# 3V3_REG.net
KiCad netlist of a schematic drawn in Altium Designer
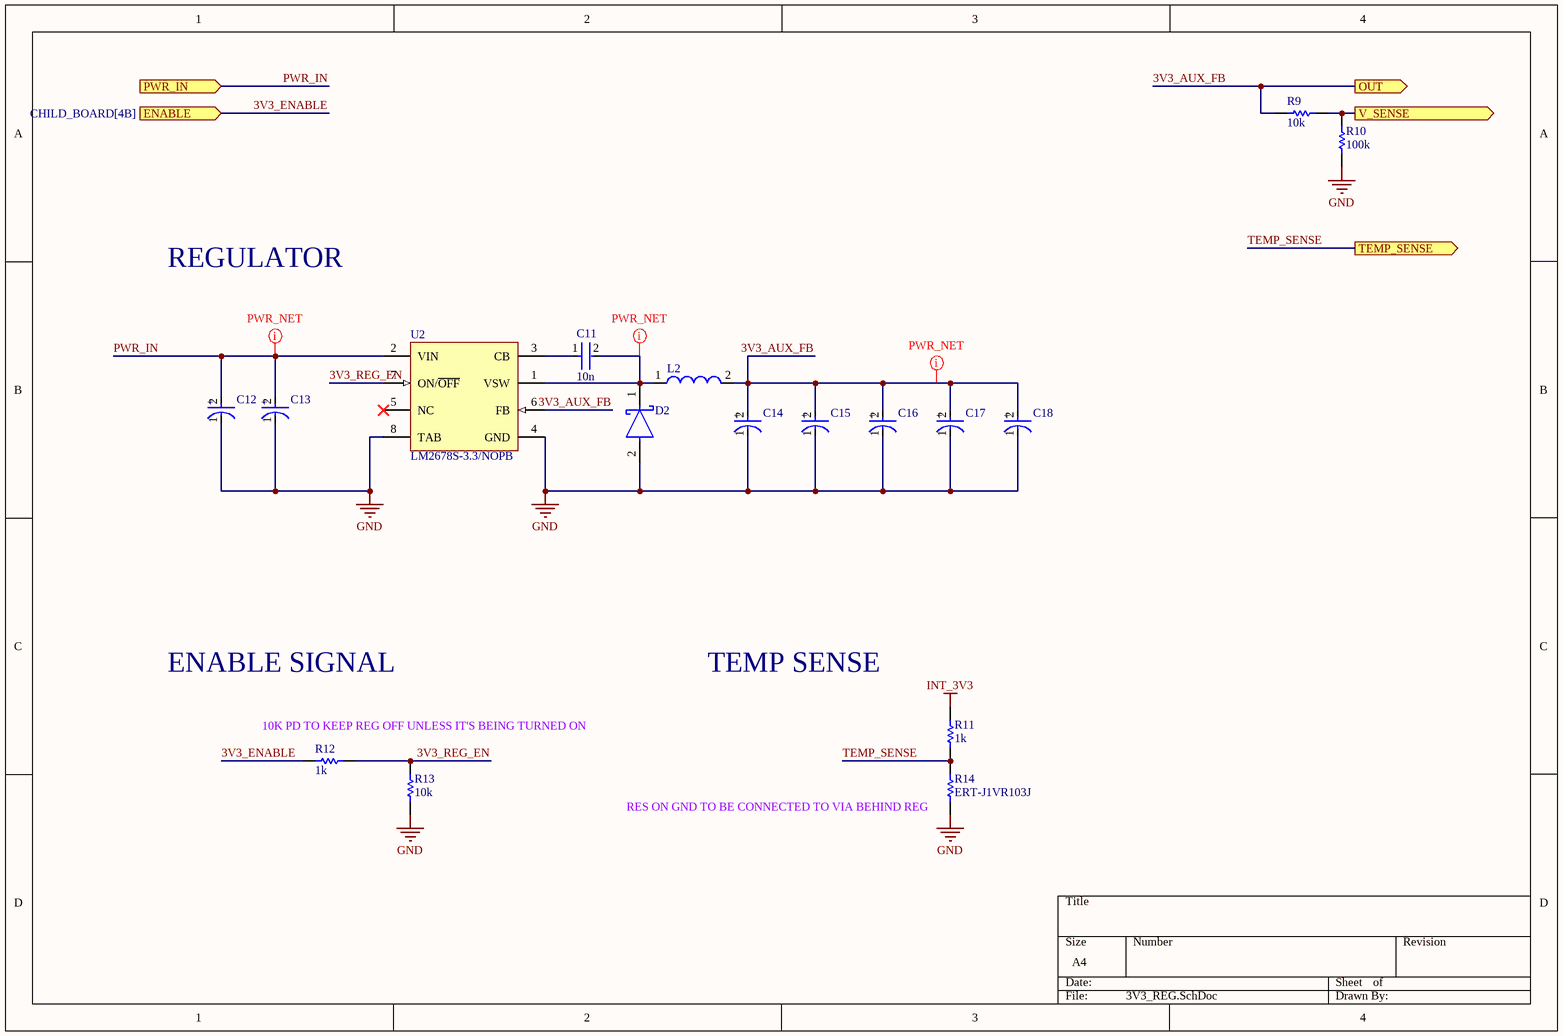
[diagram p0: 3V3_REG.SchDoc]

(export (version "E")
  (design (tool "Eeschema 10.0.6"))
  (components
    (comp (ref "C11")
      (value "10n")
      (footprint "FP-0402-L_1_0_0_05-W_0_5-IPC_A")
      (description "LARGE PADS, 0402 CAP, CHANGE COMMENT TO MATCH REAL P/N")
      (libsource (lib "Space Concordia") (part "b4654b650e69147ec39a6b967a45e02"))
    )
    (comp (ref "C12")
      (value "EEHZA1V680XP")
      (footprint "FP-EEH-D8-MFG")
      (description "Conductive Polymer Hybrid Aluminum Electrolytic Capacitors 68uF ±20% 35V RADIAL SMT 6.3x7.7mm")
      (fields (field (name "VOLTAGE") "35V") (field (name "TOLERANCE") "20%"))
      (libsource (lib "Altium Content Vault") (part "a00bbbee19879c290e62620ae7e47b1"))
    )
    (comp (ref "C13")
      (value "EEHZA1V680XP")
      (footprint "FP-EEH-D8-MFG")
      (description "Conductive Polymer Hybrid Aluminum Electrolytic Capacitors 68uF ±20% 35V RADIAL SMT 6.3x7.7mm")
      (fields (field (name "VOLTAGE") "35V") (field (name "TOLERANCE") "20%"))
      (libsource (lib "Altium Content Vault") (part "a00bbbee19879c290e62620ae7e47b1"))
    )
    (comp (ref "C14")
      (value "16SVPC120M")
      (footprint "FP-OS-CON-SMT-E7-MFG")
      (description "Conductive Polymer Aluminum Solid Capacitors (OS-CON) 120uF ±20% 16V RADIAL SMT 8x6.9mm")
      (fields (field (name "VOLTAGE") "16V") (field (name "TOLERANCE") "20%"))
      (libsource (lib "Altium Content Vault") (part "cf48714ba7e38822c1575c7ec0b6d1f"))
    )
    (comp (ref "C15")
      (value "16SVPC120M")
      (footprint "FP-OS-CON-SMT-E7-MFG")
      (description "Conductive Polymer Aluminum Solid Capacitors (OS-CON) 120uF ±20% 16V RADIAL SMT 8x6.9mm")
      (fields (field (name "VOLTAGE") "16V") (field (name "TOLERANCE") "20%"))
      (libsource (lib "Altium Content Vault") (part "cf48714ba7e38822c1575c7ec0b6d1f"))
    )
    (comp (ref "C16")
      (value "16SVPC120M")
      (footprint "FP-OS-CON-SMT-E7-MFG")
      (description "Conductive Polymer Aluminum Solid Capacitors (OS-CON) 120uF ±20% 16V RADIAL SMT 8x6.9mm")
      (fields (field (name "VOLTAGE") "16V") (field (name "TOLERANCE") "20%"))
      (libsource (lib "Altium Content Vault") (part "cf48714ba7e38822c1575c7ec0b6d1f"))
    )
    (comp (ref "C17")
      (value "16SVPC120M")
      (footprint "FP-OS-CON-SMT-E7-MFG")
      (description "Conductive Polymer Aluminum Solid Capacitors (OS-CON) 120uF ±20% 16V RADIAL SMT 8x6.9mm")
      (fields (field (name "VOLTAGE") "16V") (field (name "TOLERANCE") "20%"))
      (libsource (lib "Altium Content Vault") (part "cf48714ba7e38822c1575c7ec0b6d1f"))
    )
    (comp (ref "C18")
      (value "16SVPC120M")
      (footprint "FP-OS-CON-SMT-E7-MFG")
      (description "Conductive Polymer Aluminum Solid Capacitors (OS-CON) 120uF ±20% 16V RADIAL SMT 8x6.9mm")
      (fields (field (name "VOLTAGE") "16V") (field (name "TOLERANCE") "20%"))
      (libsource (lib "Altium Content Vault") (part "cf48714ba7e38822c1575c7ec0b6d1f"))
    )
    (comp (ref "D2")
      (value "B540C-13-F")
      (footprint "FP-SMC-MFG")
      (description "DIODE SCHOTTKY 40V 5A SMC")
      (fields
        (field (name "OCTOPART") "https://octopart.com/b540c-13-f-diodes+inc.-325873")
        (field (name "MANUFACTURER") "Diodes Inc.")
      )
      (libsource (lib "Altium Content Vault") (part "1d6ec82d83fb6aee721767c19dac4b9"))
    )
    (comp (ref "L2")
      (value "74477110")
      (footprint "WE-PD-L")
      (description "SMD-Shielded Power Inductor WE-PD, L = 10.0 µH")
      (libsource (lib "Altium Content Vault") (part "PAS-IND-INDUCTOR-2"))
    )
    (comp (ref "R9")
      (value "10k")
      (footprint "R0603B")
      (description "Resistor")
      (libsource (lib "Space Concordia") (part "Resistor"))
    )
    (comp (ref "R10")
      (value "100k")
      (footprint "R0603B")
      (description "Resistor")
      (libsource (lib "Space Concordia") (part "Resistor"))
    )
    (comp (ref "R11")
      (value "1k")
      (footprint "R0603B")
      (description "Resistor")
      (libsource (lib "Space Concordia") (part "Resistor"))
    )
    (comp (ref "R12")
      (value "1k")
      (footprint "R0603B")
      (description "Resistor")
      (libsource (lib "Space Concordia") (part "Resistor"))
    )
    (comp (ref "R13")
      (value "10k")
      (footprint "R0603B")
      (description "Resistor")
      (libsource (lib "Space Concordia") (part "Resistor"))
    )
    (comp (ref "R14")
      (value "ERT-J1VR103J")
      (footprint "RESC1608X90X30ML15T20")
      (fields (field (name "MANUFACTURER") "Panasonic"))
      (libsource (lib "Altium Content Vault") (part "RES"))
    )
    (comp (ref "U2")
      (value "LM2678S-3.3/NOPB")
      (footprint "KTW0007B_N")
      (description "SIMPLE SWITCHER® High Efficiency 5A Step-Down Voltage Regulator, 7-pin TO-263, Pb-Free")
      (fields (field (name "MANUFACTURER") "Texas Instruments"))
      (libsource (lib "Altium Content Vault") (part "PM-REG-LM2678S"))
    )
  )
  (nets
    (net (code "1") (name "/3V3_AUX_FB") (class "Default")
      (node (ref "C14") (pin "2") (pinfunction "A_2") (pintype "passive"))
      (node (ref "C15") (pin "2") (pinfunction "A_2") (pintype "passive"))
      (node (ref "C16") (pin "2") (pinfunction "A_2") (pintype "passive"))
      (node (ref "C17") (pin "2") (pinfunction "A_2") (pintype "passive"))
      (node (ref "C18") (pin "2") (pinfunction "A_2") (pintype "passive"))
      (node (ref "L2") (pin "2") (pinfunction "2_2") (pintype "passive"))
      (node (ref "R9") (pin "1") (pinfunction "1_1") (pintype "passive"))
      (node (ref "U2") (pin "6") (pinfunction "FB_6") (pintype "input"))
    )
    (net (code "2") (name "/3V3_ENABLE") (class "Default")
      (node (ref "R12") (pin "2") (pinfunction "2_2") (pintype "passive"))
    )
    (net (code "3") (name "/3V3_REG_EN") (class "Default")
      (node (ref "R12") (pin "1") (pinfunction "1_1") (pintype "passive"))
      (node (ref "R13") (pin "1") (pinfunction "1_1") (pintype "passive"))
      (node (ref "U2") (pin "7") (pinfunction "ON/~{OFF}_7") (pintype "input"))
    )
    (net (code "4") (name "/PWR_IN") (class "Default")
      (node (ref "C12") (pin "2") (pinfunction "A_2") (pintype "passive"))
      (node (ref "C13") (pin "2") (pinfunction "A_2") (pintype "passive"))
      (node (ref "U2") (pin "2") (pinfunction "VIN_2") (pintype "power_in"))
    )
    (net (code "5") (name "/TEMP_SENSE") (class "Default")
      (node (ref "R11") (pin "2") (pinfunction "2_2") (pintype "passive"))
      (node (ref "R14") (pin "2") (pinfunction "2_2") (pintype "passive"))
    )
    (net (code "6") (name "/V_SENSE") (class "Default")
      (node (ref "R10") (pin "1") (pinfunction "1_1") (pintype "passive"))
      (node (ref "R9") (pin "2") (pinfunction "2_2") (pintype "passive"))
    )
    (net (code "7") (name "GND") (class "Default")
      (node (ref "C12") (pin "1") (pinfunction "C_1") (pintype "passive"))
      (node (ref "C13") (pin "1") (pinfunction "C_1") (pintype "passive"))
      (node (ref "C14") (pin "1") (pinfunction "C_1") (pintype "passive"))
      (node (ref "C15") (pin "1") (pinfunction "C_1") (pintype "passive"))
      (node (ref "C16") (pin "1") (pinfunction "C_1") (pintype "passive"))
      (node (ref "C17") (pin "1") (pinfunction "C_1") (pintype "passive"))
      (node (ref "C18") (pin "1") (pinfunction "C_1") (pintype "passive"))
      (node (ref "D2") (pin "2") (pinfunction "A_2") (pintype "passive"))
      (node (ref "R10") (pin "2") (pinfunction "2_2") (pintype "passive"))
      (node (ref "R13") (pin "2") (pinfunction "2_2") (pintype "passive"))
      (node (ref "R14") (pin "1") (pinfunction "1_1") (pintype "passive"))
      (node (ref "U2") (pin "4") (pinfunction "GND_4") (pintype "power_in"))
      (node (ref "U2") (pin "8") (pinfunction "TAB_8") (pintype "power_in"))
    )
    (net (code "8") (name "INT_3V3") (class "Default")
      (node (ref "R11") (pin "1") (pinfunction "1_1") (pintype "passive"))
    )
    (net (code "9") (name "Net-(D2-C)") (class "Default")
      (node (ref "C11") (pin "2") (pinfunction "2_2") (pintype "passive"))
      (node (ref "D2") (pin "1") (pinfunction "C_1") (pintype "passive"))
      (node (ref "L2") (pin "1") (pinfunction "1_1") (pintype "passive"))
      (node (ref "U2") (pin "1") (pinfunction "VSW_1") (pintype "power_in"))
    )
    (net (code "10") (name "Net-(U2-CB)") (class "Default")
      (node (ref "C11") (pin "1") (pinfunction "1_1") (pintype "passive"))
      (node (ref "U2") (pin "3") (pinfunction "CB_3") (pintype "passive"))
    )
    (net (code "11") (name "unconnected-(U2-NC-Pad5)") (class "Default")
      (node (ref "U2") (pin "5") (pinfunction "NC_5") (pintype "passive+no_connect"))
    )
  )
)
